# openTPM-v12.net
KiCad netlist of a schematic drawn in EAGLE
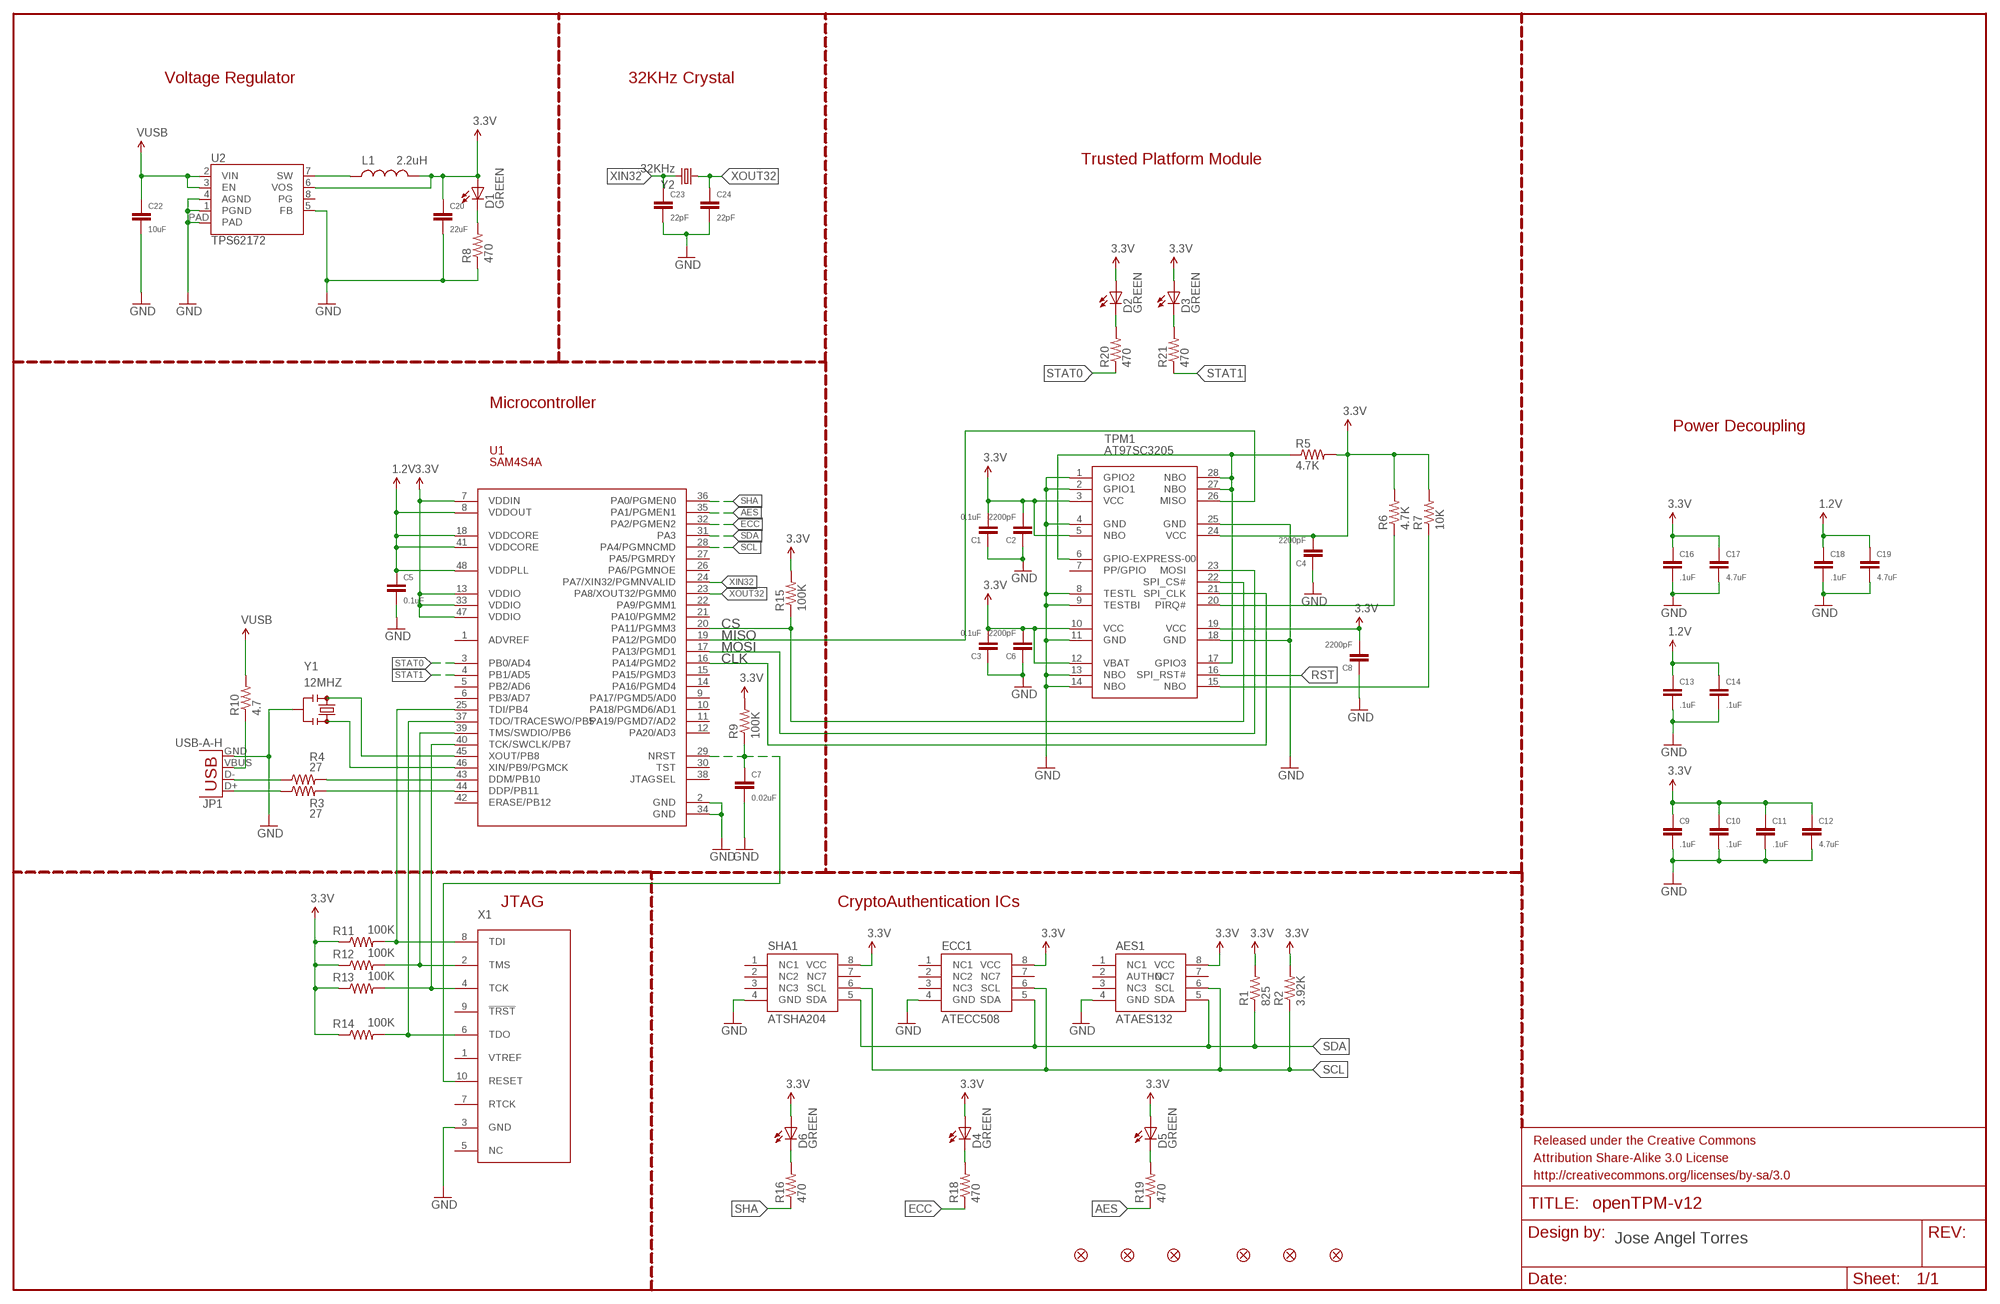
[diagram p0: schematic, sheet 1]

(export (version "E")
  (design (tool "Eeschema 10.0.6"))
  (components
    (comp (ref "AES1")
      (value "ATAES132")
      (footprint "eagle-import:CRYPTOTRONIX_SOIC8")
      (libsource (lib "eagle-import") (part "CRYPTOTRONIX_ATAES132"))
    )
    (comp (ref "C1")
      (value "0.1uF")
      (footprint "eagle-import:0201")
      (libsource (lib "eagle-import") (part "CAPACITOR.0201"))
    )
    (comp (ref "C2")
      (value "2200pF")
      (footprint "eagle-import:0201")
      (libsource (lib "eagle-import") (part "CAPACITOR.0201"))
    )
    (comp (ref "C3")
      (value "0.1uF")
      (footprint "eagle-import:0201")
      (libsource (lib "eagle-import") (part "CAPACITOR.0201"))
    )
    (comp (ref "C4")
      (value "2200pF")
      (footprint "eagle-import:0201")
      (libsource (lib "eagle-import") (part "CAPACITOR.0201"))
    )
    (comp (ref "C5")
      (value "0.1uF")
      (footprint "eagle-import:0201")
      (libsource (lib "eagle-import") (part "CAPACITOR.0201"))
    )
    (comp (ref "C6")
      (value "2200pF")
      (footprint "eagle-import:0201")
      (libsource (lib "eagle-import") (part "CAPACITOR.0201"))
    )
    (comp (ref "C7")
      (value "0.02uF")
      (footprint "eagle-import:0201")
      (libsource (lib "eagle-import") (part "CAPACITOR.0201"))
    )
    (comp (ref "C8")
      (value "2200pF")
      (footprint "eagle-import:0201")
      (libsource (lib "eagle-import") (part "CAPACITOR.0201"))
    )
    (comp (ref "C9")
      (value ".1uF")
      (footprint "eagle-import:0201")
      (libsource (lib "eagle-import") (part "CAPACITOR.0201"))
    )
    (comp (ref "C10")
      (value ".1uF")
      (footprint "eagle-import:0201")
      (libsource (lib "eagle-import") (part "CAPACITOR.0201"))
    )
    (comp (ref "C11")
      (value ".1uF")
      (footprint "eagle-import:0201")
      (libsource (lib "eagle-import") (part "CAPACITOR.0201"))
    )
    (comp (ref "C12")
      (value "4.7uF")
      (footprint "eagle-import:0402")
      (libsource (lib "eagle-import") (part "CAPACITOR.0402"))
    )
    (comp (ref "C13")
      (value ".1uF")
      (footprint "eagle-import:0201")
      (libsource (lib "eagle-import") (part "CAPACITOR.0201"))
    )
    (comp (ref "C14")
      (value ".1uF")
      (footprint "eagle-import:0201")
      (libsource (lib "eagle-import") (part "CAPACITOR.0201"))
    )
    (comp (ref "C16")
      (value ".1uF")
      (footprint "eagle-import:0201")
      (libsource (lib "eagle-import") (part "CAPACITOR.0201"))
    )
    (comp (ref "C17")
      (value "4.7uF")
      (footprint "eagle-import:0402")
      (libsource (lib "eagle-import") (part "CAPACITOR.0402"))
    )
    (comp (ref "C18")
      (value ".1uF")
      (footprint "eagle-import:0201")
      (libsource (lib "eagle-import") (part "CAPACITOR.0201"))
    )
    (comp (ref "C19")
      (value "4.7uF")
      (footprint "eagle-import:0402")
      (libsource (lib "eagle-import") (part "CAPACITOR.0402"))
    )
    (comp (ref "C20")
      (value "22uF")
      (footprint "eagle-import:0603")
      (libsource (lib "eagle-import") (part "CAPACITOR.0603"))
    )
    (comp (ref "C22")
      (value "10uF")
      (footprint "eagle-import:0402")
      (libsource (lib "eagle-import") (part "CAPACITOR.0402"))
    )
    (comp (ref "C23")
      (value "22pF")
      (footprint "eagle-import:0201")
      (libsource (lib "eagle-import") (part "CAPACITOR.0201"))
    )
    (comp (ref "C24")
      (value "22pF")
      (footprint "eagle-import:0201")
      (libsource (lib "eagle-import") (part "CAPACITOR.0201"))
    )
    (comp (ref "D1")
      (value "GREEN")
      (footprint "eagle-import:SPARKFUN-LED_LED-0603")
      (libsource (lib "eagle-import") (part "SPARKFUN-LED_LED-GREEN0603"))
    )
    (comp (ref "D2")
      (value "GREEN")
      (footprint "eagle-import:SPARKFUN-LED_LED-0603")
      (libsource (lib "eagle-import") (part "SPARKFUN-LED_LED-GREEN0603"))
    )
    (comp (ref "D3")
      (value "GREEN")
      (footprint "eagle-import:SPARKFUN-LED_LED-0603")
      (libsource (lib "eagle-import") (part "SPARKFUN-LED_LED-GREEN0603"))
    )
    (comp (ref "D4")
      (value "GREEN")
      (footprint "eagle-import:SPARKFUN-LED_LED-0603")
      (libsource (lib "eagle-import") (part "SPARKFUN-LED_LED-GREEN0603"))
    )
    (comp (ref "D5")
      (value "GREEN")
      (footprint "eagle-import:SPARKFUN-LED_LED-0603")
      (libsource (lib "eagle-import") (part "SPARKFUN-LED_LED-GREEN0603"))
    )
    (comp (ref "D6")
      (value "GREEN")
      (footprint "eagle-import:SPARKFUN-LED_LED-0603")
      (libsource (lib "eagle-import") (part "SPARKFUN-LED_LED-GREEN0603"))
    )
    (comp (ref "ECC1")
      (value "ATECC508")
      (footprint "eagle-import:CRYPTOTRONIX_SOIC8")
      (libsource (lib "eagle-import") (part "ATECC508"))
    )
    (comp (ref "FID1")
      (value "SPARKFUN-AESTHETICS_FIDUCIAL1X2")
      (footprint "eagle-import:SPARKFUN-AESTHETICS_FIDUCIAL-1X2")
      (libsource (lib "eagle-import") (part "SPARKFUN-AESTHETICS_FIDUCIAL1X2"))
    )
    (comp (ref "FID2")
      (value "SPARKFUN-AESTHETICS_FIDUCIAL1X2")
      (footprint "eagle-import:SPARKFUN-AESTHETICS_FIDUCIAL-1X2")
      (libsource (lib "eagle-import") (part "SPARKFUN-AESTHETICS_FIDUCIAL1X2"))
    )
    (comp (ref "FID3")
      (value "SPARKFUN-AESTHETICS_FIDUCIAL1X2")
      (footprint "eagle-import:SPARKFUN-AESTHETICS_FIDUCIAL-1X2")
      (libsource (lib "eagle-import") (part "SPARKFUN-AESTHETICS_FIDUCIAL1X2"))
    )
    (comp (ref "FID4")
      (value "SPARKFUN-AESTHETICS_FIDUCIAL1X2")
      (footprint "eagle-import:SPARKFUN-AESTHETICS_FIDUCIAL-1X2")
      (libsource (lib "eagle-import") (part "SPARKFUN-AESTHETICS_FIDUCIAL1X2"))
    )
    (comp (ref "FID5")
      (value "SPARKFUN-AESTHETICS_FIDUCIAL1X2")
      (footprint "eagle-import:SPARKFUN-AESTHETICS_FIDUCIAL-1X2")
      (libsource (lib "eagle-import") (part "SPARKFUN-AESTHETICS_FIDUCIAL1X2"))
    )
    (comp (ref "FID6")
      (value "SPARKFUN-AESTHETICS_FIDUCIAL1X2")
      (footprint "eagle-import:SPARKFUN-AESTHETICS_FIDUCIAL-1X2")
      (libsource (lib "eagle-import") (part "SPARKFUN-AESTHETICS_FIDUCIAL1X2"))
    )
    (comp (ref "JP1")
      (value "USB-A-H")
      (footprint "eagle-import:USB-A-H")
      (libsource (lib "eagle-import") (part "USB-A-H"))
    )
    (comp (ref "L1")
      (value "2.2uH")
      (footprint "eagle-import:C0402")
      (libsource (lib "eagle-import") (part "INDUCTOR0402"))
    )
    (comp (ref "R1")
      (value "825")
      (footprint "eagle-import:0201")
      (libsource (lib "eagle-import") (part "RESISTOR.0201"))
    )
    (comp (ref "R2")
      (value "3.92K")
      (footprint "eagle-import:0201")
      (libsource (lib "eagle-import") (part "RESISTOR.0201"))
    )
    (comp (ref "R3")
      (value "27")
      (footprint "eagle-import:0402")
      (libsource (lib "eagle-import") (part "RESISTOR.0402"))
    )
    (comp (ref "R4")
      (value "27")
      (footprint "eagle-import:0402")
      (libsource (lib "eagle-import") (part "RESISTOR.0402"))
    )
    (comp (ref "R5")
      (value "4.7K")
      (footprint "eagle-import:0201")
      (libsource (lib "eagle-import") (part "RESISTOR.0201"))
    )
    (comp (ref "R6")
      (value "4.7K")
      (footprint "eagle-import:0201")
      (libsource (lib "eagle-import") (part "RESISTOR.0201"))
    )
    (comp (ref "R7")
      (value "10K")
      (footprint "eagle-import:0201")
      (libsource (lib "eagle-import") (part "RESISTOR.0201"))
    )
    (comp (ref "R8")
      (value "470")
      (footprint "eagle-import:0402")
      (libsource (lib "eagle-import") (part "RESISTOR.0402"))
    )
    (comp (ref "R9")
      (value "100K")
      (footprint "eagle-import:0201")
      (libsource (lib "eagle-import") (part "RESISTOR.0201"))
    )
    (comp (ref "R10")
      (value "4.7")
      (footprint "eagle-import:0402")
      (libsource (lib "eagle-import") (part "RESISTOR.0402"))
    )
    (comp (ref "R11")
      (value "100K")
      (footprint "eagle-import:0201")
      (libsource (lib "eagle-import") (part "RESISTOR.0201"))
    )
    (comp (ref "R12")
      (value "100K")
      (footprint "eagle-import:0201")
      (libsource (lib "eagle-import") (part "RESISTOR.0201"))
    )
    (comp (ref "R13")
      (value "100K")
      (footprint "eagle-import:0201")
      (libsource (lib "eagle-import") (part "RESISTOR.0201"))
    )
    (comp (ref "R14")
      (value "100K")
      (footprint "eagle-import:0201")
      (libsource (lib "eagle-import") (part "RESISTOR.0201"))
    )
    (comp (ref "R15")
      (value "100K")
      (footprint "eagle-import:0201")
      (libsource (lib "eagle-import") (part "RESISTOR.0201"))
    )
    (comp (ref "R16")
      (value "470")
      (footprint "eagle-import:0201")
      (libsource (lib "eagle-import") (part "RESISTOR.0201"))
    )
    (comp (ref "R18")
      (value "470")
      (footprint "eagle-import:0201")
      (libsource (lib "eagle-import") (part "RESISTOR.0201"))
    )
    (comp (ref "R19")
      (value "470")
      (footprint "eagle-import:0201")
      (libsource (lib "eagle-import") (part "RESISTOR.0201"))
    )
    (comp (ref "R20")
      (value "470")
      (footprint "eagle-import:0201")
      (libsource (lib "eagle-import") (part "RESISTOR.0201"))
    )
    (comp (ref "R21")
      (value "470")
      (footprint "eagle-import:0201")
      (libsource (lib "eagle-import") (part "RESISTOR.0201"))
    )
    (comp (ref "SHA1")
      (value "ATSHA204")
      (footprint "eagle-import:CRYPTOTRONIX_SOIC8")
      (libsource (lib "eagle-import") (part "CRYPTOTRONIX_ATSHA204"))
    )
    (comp (ref "TPM1")
      (value "AT97SC3205")
      (footprint "eagle-import:TSSOP28")
      (libsource (lib "eagle-import") (part "AT97SC3205"))
    )
    (comp (ref "U1")
      (value "SAM4S4A")
      (footprint "eagle-import:LQFP-48")
      (libsource (lib "eagle-import") (part "SAM4S4A"))
    )
    (comp (ref "U2")
      (value "TPS62172")
      (footprint "eagle-import:WSON-8-PAD")
      (libsource (lib "eagle-import") (part "TPS62172"))
    )
    (comp (ref "X1")
      (value "TC2050-NL-MCP-NL")
      (footprint "eagle-import:TC2030-MCP-NL")
      (libsource (lib "eagle-import") (part "TC2050-NL-MCP-NL"))
    )
    (comp (ref "Y1")
      (value "12MHZ")
      (footprint "eagle-import:RESONATOR-SMD")
      (libsource (lib "eagle-import") (part "RESONATOR12MHZ"))
    )
    (comp (ref "Y2")
      (value "32KHz")
      (footprint "eagle-import:CRYSTAL-32KHZ-SMD_EPSON_MC146")
      (libsource (lib "eagle-import") (part "CRYSTALEPSONMC146"))
    )
  )
  (nets
    (net (code "1") (name "/CLK") (class "Default")
      (node (ref "TPM1") (pin "21") (pinfunction "SPI_CLK_21") (pintype "bidirectional"))
      (node (ref "U1") (pin "16") (pinfunction "PA14/PGMD2_16") (pintype "bidirectional"))
    )
    (net (code "2") (name "/CS") (class "Default")
      (node (ref "R15") (pin "1") (pinfunction "1_1") (pintype "passive"))
      (node (ref "TPM1") (pin "22") (pinfunction "SPI_CS#_22") (pintype "power_in"))
      (node (ref "U1") (pin "20") (pinfunction "PA11/PGMM3_20") (pintype "bidirectional"))
    )
    (net (code "3") (name "/MISO") (class "Default")
      (node (ref "TPM1") (pin "26") (pinfunction "MISO_26") (pintype "power_in"))
      (node (ref "U1") (pin "19") (pinfunction "PA12/PGMD0_19") (pintype "bidirectional"))
    )
    (net (code "4") (name "/MOSI") (class "Default")
      (node (ref "TPM1") (pin "23") (pinfunction "MOSI_23") (pintype "power_in"))
      (node (ref "U1") (pin "17") (pinfunction "PA13/PGMD1_17") (pintype "bidirectional"))
    )
    (net (code "5") (name "1.2V") (class "Default")
      (node (ref "C13") (pin "1") (pinfunction "1_1") (pintype "passive"))
      (node (ref "C14") (pin "1") (pinfunction "1_1") (pintype "passive"))
      (node (ref "C18") (pin "1") (pinfunction "1_1") (pintype "passive"))
      (node (ref "C19") (pin "1") (pinfunction "1_1") (pintype "passive"))
      (node (ref "C5") (pin "1") (pinfunction "1_1") (pintype "passive"))
      (node (ref "U1") (pin "18") (pinfunction "VDDCORE_18") (pintype "bidirectional"))
      (node (ref "U1") (pin "41") (pinfunction "VDDCORE_41") (pintype "bidirectional"))
      (node (ref "U1") (pin "48") (pinfunction "VDDPLL_48") (pintype "bidirectional"))
      (node (ref "U1") (pin "8") (pinfunction "VDDOUT_8") (pintype "bidirectional"))
    )
    (net (code "6") (name "3.3V") (class "Default")
      (node (ref "AES1") (pin "8") (pinfunction "VCC_8") (pintype "power_in"))
      (node (ref "C1") (pin "2") (pinfunction "2_2") (pintype "passive"))
      (node (ref "C10") (pin "1") (pinfunction "1_1") (pintype "passive"))
      (node (ref "C11") (pin "1") (pinfunction "1_1") (pintype "passive"))
      (node (ref "C12") (pin "1") (pinfunction "1_1") (pintype "passive"))
      (node (ref "C16") (pin "1") (pinfunction "1_1") (pintype "passive"))
      (node (ref "C17") (pin "1") (pinfunction "1_1") (pintype "passive"))
      (node (ref "C2") (pin "2") (pinfunction "2_2") (pintype "passive"))
      (node (ref "C20") (pin "1") (pinfunction "1_1") (pintype "passive"))
      (node (ref "C3") (pin "2") (pinfunction "2_2") (pintype "passive"))
      (node (ref "C4") (pin "2") (pinfunction "2_2") (pintype "passive"))
      (node (ref "C6") (pin "2") (pinfunction "2_2") (pintype "passive"))
      (node (ref "C8") (pin "2") (pinfunction "2_2") (pintype "passive"))
      (node (ref "C9") (pin "1") (pinfunction "1_1") (pintype "passive"))
      (node (ref "D1") (pin "A") (pinfunction "A_A") (pintype "passive"))
      (node (ref "D2") (pin "A") (pinfunction "A_A") (pintype "passive"))
      (node (ref "D3") (pin "A") (pinfunction "A_A") (pintype "passive"))
      (node (ref "D4") (pin "A") (pinfunction "A_A") (pintype "passive"))
      (node (ref "D5") (pin "A") (pinfunction "A_A") (pintype "passive"))
      (node (ref "D6") (pin "A") (pinfunction "A_A") (pintype "passive"))
      (node (ref "ECC1") (pin "8") (pinfunction "VCC_8") (pintype "power_in"))
      (node (ref "L1") (pin "2") (pinfunction "2_2") (pintype "passive"))
      (node (ref "R1") (pin "2") (pinfunction "2_2") (pintype "passive"))
      (node (ref "R11") (pin "1") (pinfunction "1_1") (pintype "passive"))
      (node (ref "R12") (pin "1") (pinfunction "1_1") (pintype "passive"))
      (node (ref "R13") (pin "1") (pinfunction "1_1") (pintype "passive"))
      (node (ref "R14") (pin "1") (pinfunction "1_1") (pintype "passive"))
      (node (ref "R15") (pin "2") (pinfunction "2_2") (pintype "passive"))
      (node (ref "R2") (pin "2") (pinfunction "2_2") (pintype "passive"))
      (node (ref "R5") (pin "2") (pinfunction "2_2") (pintype "passive"))
      (node (ref "R6") (pin "2") (pinfunction "2_2") (pintype "passive"))
      (node (ref "R7") (pin "2") (pinfunction "2_2") (pintype "passive"))
      (node (ref "R9") (pin "2") (pinfunction "2_2") (pintype "passive"))
      (node (ref "SHA1") (pin "8") (pinfunction "VCC_8") (pintype "power_in"))
      (node (ref "TPM1") (pin "10") (pinfunction "VCC_10") (pintype "power_in"))
      (node (ref "TPM1") (pin "12") (pinfunction "VBAT_12") (pintype "bidirectional"))
      (node (ref "TPM1") (pin "19") (pinfunction "VCC_19") (pintype "power_in"))
      (node (ref "TPM1") (pin "24") (pinfunction "VCC_24") (pintype "power_in"))
      (node (ref "TPM1") (pin "3") (pinfunction "VCC_3") (pintype "power_in"))
      (node (ref "TPM1") (pin "5") (pinfunction "NBO_5") (pintype "bidirectional"))
      (node (ref "U1") (pin "13") (pinfunction "VDDIO_13") (pintype "bidirectional"))
      (node (ref "U1") (pin "33") (pinfunction "VDDIO_33") (pintype "bidirectional"))
      (node (ref "U1") (pin "47") (pinfunction "VDDIO_47") (pintype "bidirectional"))
      (node (ref "U1") (pin "7") (pinfunction "VDDIN_7") (pintype "bidirectional"))
      (node (ref "U2") (pin "6") (pinfunction "VOS_6") (pintype "bidirectional"))
    )
    (net (code "7") (name "AES") (class "Default")
      (node (ref "R19") (pin "1") (pinfunction "1_1") (pintype "passive"))
      (node (ref "U1") (pin "35") (pinfunction "PA1/PGMEN1_35") (pintype "bidirectional"))
    )
    (net (code "8") (name "ECC") (class "Default")
      (node (ref "R18") (pin "1") (pinfunction "1_1") (pintype "passive"))
      (node (ref "U1") (pin "32") (pinfunction "PA2/PGMEN2_32") (pintype "bidirectional"))
    )
    (net (code "9") (name "GND") (class "Default")
      (node (ref "AES1") (pin "4") (pinfunction "GND_4") (pintype "power_in"))
      (node (ref "C1") (pin "1") (pinfunction "1_1") (pintype "passive"))
      (node (ref "C10") (pin "2") (pinfunction "2_2") (pintype "passive"))
      (node (ref "C11") (pin "2") (pinfunction "2_2") (pintype "passive"))
      (node (ref "C12") (pin "2") (pinfunction "2_2") (pintype "passive"))
      (node (ref "C13") (pin "2") (pinfunction "2_2") (pintype "passive"))
      (node (ref "C14") (pin "2") (pinfunction "2_2") (pintype "passive"))
      (node (ref "C16") (pin "2") (pinfunction "2_2") (pintype "passive"))
      (node (ref "C17") (pin "2") (pinfunction "2_2") (pintype "passive"))
      (node (ref "C18") (pin "2") (pinfunction "2_2") (pintype "passive"))
      (node (ref "C19") (pin "2") (pinfunction "2_2") (pintype "passive"))
      (node (ref "C2") (pin "1") (pinfunction "1_1") (pintype "passive"))
      (node (ref "C20") (pin "2") (pinfunction "2_2") (pintype "passive"))
      (node (ref "C22") (pin "2") (pinfunction "2_2") (pintype "passive"))
      (node (ref "C23") (pin "2") (pinfunction "2_2") (pintype "passive"))
      (node (ref "C24") (pin "2") (pinfunction "2_2") (pintype "passive"))
      (node (ref "C3") (pin "1") (pinfunction "1_1") (pintype "passive"))
      (node (ref "C4") (pin "1") (pinfunction "1_1") (pintype "passive"))
      (node (ref "C5") (pin "2") (pinfunction "2_2") (pintype "passive"))
      (node (ref "C6") (pin "1") (pinfunction "1_1") (pintype "passive"))
      (node (ref "C7") (pin "2") (pinfunction "2_2") (pintype "passive"))
      (node (ref "C8") (pin "1") (pinfunction "1_1") (pintype "passive"))
      (node (ref "C9") (pin "2") (pinfunction "2_2") (pintype "passive"))
      (node (ref "ECC1") (pin "4") (pinfunction "GND_4") (pintype "power_in"))
      (node (ref "JP1") (pin "GND") (pinfunction "GND_GND") (pintype "bidirectional"))
      (node (ref "R8") (pin "1") (pinfunction "1_1") (pintype "passive"))
      (node (ref "SHA1") (pin "4") (pinfunction "GND_4") (pintype "power_in"))
      (node (ref "TPM1") (pin "1") (pinfunction "GPIO2_1") (pintype "bidirectional"))
      (node (ref "TPM1") (pin "11") (pinfunction "GND_11") (pintype "power_in"))
      (node (ref "TPM1") (pin "13") (pinfunction "NBO_13") (pintype "bidirectional"))
      (node (ref "TPM1") (pin "14") (pinfunction "NBO_14") (pintype "bidirectional"))
      (node (ref "TPM1") (pin "18") (pinfunction "GND_18") (pintype "power_in"))
      (node (ref "TPM1") (pin "2") (pinfunction "GPIO1_2") (pintype "bidirectional"))
      (node (ref "TPM1") (pin "25") (pinfunction "GND_25") (pintype "power_in"))
      (node (ref "TPM1") (pin "4") (pinfunction "GND_4") (pintype "power_in"))
      (node (ref "TPM1") (pin "8") (pinfunction "TESTL_8") (pintype "bidirectional"))
      (node (ref "TPM1") (pin "9") (pinfunction "TESTBI_9") (pintype "bidirectional"))
      (node (ref "U1") (pin "2") (pinfunction "GND_2") (pintype "bidirectional"))
      (node (ref "U1") (pin "34") (pinfunction "GND_34") (pintype "bidirectional"))
      (node (ref "U2") (pin "1") (pinfunction "PGND_1") (pintype "bidirectional"))
      (node (ref "U2") (pin "4") (pinfunction "AGND_4") (pintype "bidirectional"))
      (node (ref "U2") (pin "5") (pinfunction "FB_5") (pintype "bidirectional"))
      (node (ref "U2") (pin "PAD") (pinfunction "PAD_PAD") (pintype "bidirectional"))
      (node (ref "X1") (pin "3") (pinfunction "GND_3") (pintype "bidirectional"))
      (node (ref "Y1") (pin "2") (pinfunction "2_2") (pintype "passive"))
    )
    (net (code "10") (name "Net-(D1-PadC)") (class "Default")
      (node (ref "D1") (pin "C") (pinfunction "C_C") (pintype "passive"))
      (node (ref "R8") (pin "2") (pinfunction "2_2") (pintype "passive"))
    )
    (net (code "11") (name "Net-(D2-PadC)") (class "Default")
      (node (ref "D2") (pin "C") (pinfunction "C_C") (pintype "passive"))
      (node (ref "R20") (pin "2") (pinfunction "2_2") (pintype "passive"))
    )
    (net (code "12") (name "Net-(D3-PadC)") (class "Default")
      (node (ref "D3") (pin "C") (pinfunction "C_C") (pintype "passive"))
      (node (ref "R21") (pin "2") (pinfunction "2_2") (pintype "passive"))
    )
    (net (code "13") (name "Net-(D4-PadC)") (class "Default")
      (node (ref "D4") (pin "C") (pinfunction "C_C") (pintype "passive"))
      (node (ref "R18") (pin "2") (pinfunction "2_2") (pintype "passive"))
    )
    (net (code "14") (name "Net-(D5-PadC)") (class "Default")
      (node (ref "D5") (pin "C") (pinfunction "C_C") (pintype "passive"))
      (node (ref "R19") (pin "2") (pinfunction "2_2") (pintype "passive"))
    )
    (net (code "15") (name "Net-(D6-PadC)") (class "Default")
      (node (ref "D6") (pin "C") (pinfunction "C_C") (pintype "passive"))
      (node (ref "R16") (pin "2") (pinfunction "2_2") (pintype "passive"))
    )
    (net (code "16") (name "Net-(JP1-PadD+)") (class "Default")
      (node (ref "JP1") (pin "D+") (pinfunction "D+_D+") (pintype "bidirectional"))
      (node (ref "R3") (pin "1") (pinfunction "1_1") (pintype "passive"))
    )
    (net (code "17") (name "Net-(JP1-PadD-)") (class "Default")
      (node (ref "JP1") (pin "D-") (pinfunction "D-_D-") (pintype "bidirectional"))
      (node (ref "R4") (pin "1") (pinfunction "1_1") (pintype "passive"))
    )
    (net (code "18") (name "Net-(JP1-PadVBUS)") (class "Default")
      (node (ref "JP1") (pin "VBUS") (pinfunction "VBUS_VBUS") (pintype "bidirectional"))
      (node (ref "R10") (pin "1") (pinfunction "1_1") (pintype "passive"))
    )
    (net (code "19") (name "Net-(R7-Pad1)") (class "Default")
      (node (ref "R7") (pin "1") (pinfunction "1_1") (pintype "passive"))
      (node (ref "TPM1") (pin "15") (pinfunction "NBO_15") (pintype "bidirectional"))
    )
    (net (code "20") (name "Net-(TPM1-GPIO-EXPRESS-00)") (class "Default")
      (node (ref "R5") (pin "1") (pinfunction "1_1") (pintype "passive"))
      (node (ref "TPM1") (pin "17") (pinfunction "GPIO3_17") (pintype "power_in"))
      (node (ref "TPM1") (pin "27") (pinfunction "NBO_27") (pintype "bidirectional"))
      (node (ref "TPM1") (pin "28") (pinfunction "NBO_28") (pintype "bidirectional"))
      (node (ref "TPM1") (pin "6") (pinfunction "GPIO-EXPRESS-00_6") (pintype "power_in"))
    )
    (net (code "21") (name "Net-(TPM1-PIRQ#)") (class "Default")
      (node (ref "R6") (pin "1") (pinfunction "1_1") (pintype "passive"))
      (node (ref "TPM1") (pin "20") (pinfunction "PIRQ#_20") (pintype "power_in"))
    )
    (net (code "22") (name "Net-(U1-DDM{slash}PB10)") (class "Default")
      (node (ref "R4") (pin "2") (pinfunction "2_2") (pintype "passive"))
      (node (ref "U1") (pin "43") (pinfunction "DDM/PB10_43") (pintype "bidirectional"))
    )
    (net (code "23") (name "Net-(U1-DDP{slash}PB11)") (class "Default")
      (node (ref "R3") (pin "2") (pinfunction "2_2") (pintype "passive"))
      (node (ref "U1") (pin "44") (pinfunction "DDP/PB11_44") (pintype "bidirectional"))
    )
    (net (code "24") (name "Net-(U1-TCK{slash}SWCLK{slash}PB7)") (class "Default")
      (node (ref "R13") (pin "2") (pinfunction "2_2") (pintype "passive"))
      (node (ref "U1") (pin "40") (pinfunction "TCK/SWCLK/PB7_40") (pintype "bidirectional"))
      (node (ref "X1") (pin "4") (pinfunction "TCK_4") (pintype "bidirectional"))
    )
    (net (code "25") (name "Net-(U1-TDI{slash}PB4)") (class "Default")
      (node (ref "R11") (pin "2") (pinfunction "2_2") (pintype "passive"))
      (node (ref "U1") (pin "25") (pinfunction "TDI/PB4_25") (pintype "bidirectional"))
      (node (ref "X1") (pin "8") (pinfunction "TDI_8") (pintype "bidirectional"))
    )
    (net (code "26") (name "Net-(U1-TDO{slash}TRACESWO{slash}PB5)") (class "Default")
      (node (ref "R14") (pin "2") (pinfunction "2_2") (pintype "passive"))
      (node (ref "U1") (pin "37") (pinfunction "TDO/TRACESWO/PB5_37") (pintype "bidirectional"))
      (node (ref "X1") (pin "6") (pinfunction "TDO_6") (pintype "bidirectional"))
    )
    (net (code "27") (name "Net-(U1-TMS{slash}SWDIO{slash}PB6)") (class "Default")
      (node (ref "R12") (pin "2") (pinfunction "2_2") (pintype "passive"))
      (node (ref "U1") (pin "39") (pinfunction "TMS/SWDIO/PB6_39") (pintype "bidirectional"))
      (node (ref "X1") (pin "2") (pinfunction "TMS_2") (pintype "bidirectional"))
    )
    (net (code "28") (name "Net-(U1-XIN{slash}PB9{slash}PGMCK)") (class "Default")
      (node (ref "U1") (pin "46") (pinfunction "XIN/PB9/PGMCK_46") (pintype "bidirectional"))
      (node (ref "Y1") (pin "3") (pinfunction "3_3") (pintype "passive"))
    )
    (net (code "29") (name "Net-(U1-XOUT{slash}PB8)") (class "Default")
      (node (ref "U1") (pin "45") (pinfunction "XOUT/PB8_45") (pintype "bidirectional"))
      (node (ref "Y1") (pin "1") (pinfunction "1_1") (pintype "passive"))
    )
    (net (code "30") (name "Net-(U2-SW)") (class "Default")
      (node (ref "L1") (pin "1") (pinfunction "1_1") (pintype "passive"))
      (node (ref "U2") (pin "7") (pinfunction "SW_7") (pintype "bidirectional"))
    )
    (net (code "31") (name "RST") (class "Default")
      (node (ref "C7") (pin "1") (pinfunction "1_1") (pintype "passive"))
      (node (ref "R9") (pin "1") (pinfunction "1_1") (pintype "passive"))
      (node (ref "TPM1") (pin "16") (pinfunction "SPI_RST#_16") (pintype "bidirectional"))
      (node (ref "U1") (pin "29") (pinfunction "NRST_29") (pintype "bidirectional"))
      (node (ref "X1") (pin "10") (pinfunction "RESET_10") (pintype "bidirectional"))
    )
    (net (code "32") (name "SCL") (class "Default")
      (node (ref "AES1") (pin "6") (pinfunction "SCL_6") (pintype "bidirectional"))
      (node (ref "ECC1") (pin "6") (pinfunction "SCL_6") (pintype "bidirectional"))
      (node (ref "R2") (pin "1") (pinfunction "1_1") (pintype "passive"))
      (node (ref "SHA1") (pin "6") (pinfunction "SCL_6") (pintype "bidirectional"))
      (node (ref "U1") (pin "28") (pinfunction "PA4/PGMNCMD_28") (pintype "bidirectional"))
    )
    (net (code "33") (name "SDA") (class "Default")
      (node (ref "AES1") (pin "5") (pinfunction "SDA_5") (pintype "bidirectional"))
      (node (ref "ECC1") (pin "5") (pinfunction "SDA_5") (pintype "bidirectional"))
      (node (ref "R1") (pin "1") (pinfunction "1_1") (pintype "passive"))
      (node (ref "SHA1") (pin "5") (pinfunction "SDA_5") (pintype "bidirectional"))
      (node (ref "U1") (pin "31") (pinfunction "PA3_31") (pintype "bidirectional"))
    )
    (net (code "34") (name "SHA") (class "Default")
      (node (ref "R16") (pin "1") (pinfunction "1_1") (pintype "passive"))
      (node (ref "U1") (pin "36") (pinfunction "PA0/PGMEN0_36") (pintype "bidirectional"))
    )
    (net (code "35") (name "STAT0") (class "Default")
      (node (ref "R20") (pin "1") (pinfunction "1_1") (pintype "passive"))
      (node (ref "U1") (pin "3") (pinfunction "PB0/AD4_3") (pintype "bidirectional"))
    )
    (net (code "36") (name "STAT1") (class "Default")
      (node (ref "R21") (pin "1") (pinfunction "1_1") (pintype "passive"))
      (node (ref "U1") (pin "4") (pinfunction "PB1/AD5_4") (pintype "bidirectional"))
    )
    (net (code "37") (name "VUSB") (class "Default")
      (node (ref "C22") (pin "1") (pinfunction "1_1") (pintype "passive"))
      (node (ref "R10") (pin "2") (pinfunction "2_2") (pintype "passive"))
      (node (ref "U2") (pin "2") (pinfunction "VIN_2") (pintype "bidirectional"))
      (node (ref "U2") (pin "3") (pinfunction "EN_3") (pintype "bidirectional"))
    )
    (net (code "38") (name "XIN32") (class "Default")
      (node (ref "C23") (pin "1") (pinfunction "1_1") (pintype "passive"))
      (node (ref "U1") (pin "24") (pinfunction "PA7/XIN32/PGMNVALID_24") (pintype "bidirectional"))
      (node (ref "Y2") (pin "P$1") (pinfunction "2_P$1") (pintype "passive"))
    )
    (net (code "39") (name "XOUT32") (class "Default")
      (node (ref "C24") (pin "1") (pinfunction "1_1") (pintype "passive"))
      (node (ref "U1") (pin "23") (pinfunction "PA8/XOUT32/PGMM0_23") (pintype "bidirectional"))
      (node (ref "Y2") (pin "P$2") (pinfunction "1_P$2") (pintype "passive"))
    )
    (net (code "40") (name "unconnected-(AES1-AUTHO-Pad2)") (class "Default")
      (node (ref "AES1") (pin "2") (pinfunction "AUTHO_2") (pintype "bidirectional"))
    )
    (net (code "41") (name "unconnected-(AES1-NC1-Pad1)") (class "Default")
      (node (ref "AES1") (pin "1") (pinfunction "NC1_1") (pintype "no_connect"))
    )
    (net (code "42") (name "unconnected-(AES1-NC3-Pad3)") (class "Default")
      (node (ref "AES1") (pin "3") (pinfunction "NC3_3") (pintype "no_connect"))
    )
    (net (code "43") (name "unconnected-(AES1-NC7-Pad7)") (class "Default")
      (node (ref "AES1") (pin "7") (pinfunction "NC7_7") (pintype "no_connect"))
    )
    (net (code "44") (name "unconnected-(ECC1-NC1-Pad1)") (class "Default")
      (node (ref "ECC1") (pin "1") (pinfunction "NC1_1") (pintype "bidirectional"))
    )
    (net (code "45") (name "unconnected-(ECC1-NC2-Pad2)") (class "Default")
      (node (ref "ECC1") (pin "2") (pinfunction "NC2_2") (pintype "no_connect"))
    )
    (net (code "46") (name "unconnected-(ECC1-NC3-Pad3)") (class "Default")
      (node (ref "ECC1") (pin "3") (pinfunction "NC3_3") (pintype "no_connect"))
    )
    (net (code "47") (name "unconnected-(ECC1-NC7-Pad7)") (class "Default")
      (node (ref "ECC1") (pin "7") (pinfunction "NC7_7") (pintype "no_connect"))
    )
    (net (code "48") (name "unconnected-(SHA1-NC1-Pad1)") (class "Default")
      (node (ref "SHA1") (pin "1") (pinfunction "NC1_1") (pintype "no_connect"))
    )
    (net (code "49") (name "unconnected-(SHA1-NC2-Pad2)") (class "Default")
      (node (ref "SHA1") (pin "2") (pinfunction "NC2_2") (pintype "no_connect"))
    )
    (net (code "50") (name "unconnected-(SHA1-NC3-Pad3)") (class "Default")
      (node (ref "SHA1") (pin "3") (pinfunction "NC3_3") (pintype "no_connect"))
    )
    (net (code "51") (name "unconnected-(SHA1-NC7-Pad7)") (class "Default")
      (node (ref "SHA1") (pin "7") (pinfunction "NC7_7") (pintype "no_connect"))
    )
    (net (code "52") (name "unconnected-(TPM1-PP{slash}GPIO-Pad7)") (class "Default")
      (node (ref "TPM1") (pin "7") (pinfunction "PP/GPIO_7") (pintype "bidirectional"))
    )
    (net (code "53") (name "unconnected-(U1-ADVREF-Pad1)") (class "Default")
      (node (ref "U1") (pin "1") (pinfunction "ADVREF_1") (pintype "bidirectional"))
    )
    (net (code "54") (name "unconnected-(U1-ERASE{slash}PB12-Pad42)") (class "Default")
      (node (ref "U1") (pin "42") (pinfunction "ERASE/PB12_42") (pintype "bidirectional"))
    )
    (net (code "55") (name "unconnected-(U1-JTAGSEL-Pad38)") (class "Default")
      (node (ref "U1") (pin "38") (pinfunction "JTAGSEL_38") (pintype "bidirectional"))
    )
    (net (code "56") (name "unconnected-(U1-PA5{slash}PGMRDY-Pad27)") (class "Default")
      (node (ref "U1") (pin "27") (pinfunction "PA5/PGMRDY_27") (pintype "bidirectional"))
    )
    (net (code "57") (name "unconnected-(U1-PA6{slash}PGMNOE-Pad26)") (class "Default")
      (node (ref "U1") (pin "26") (pinfunction "PA6/PGMNOE_26") (pintype "bidirectional"))
    )
    (net (code "58") (name "unconnected-(U1-PA9{slash}PGMM1-Pad22)") (class "Default")
      (node (ref "U1") (pin "22") (pinfunction "PA9/PGMM1_22") (pintype "bidirectional"))
    )
    (net (code "59") (name "unconnected-(U1-PA10{slash}PGMM2-Pad21)") (class "Default")
      (node (ref "U1") (pin "21") (pinfunction "PA10/PGMM2_21") (pintype "bidirectional"))
    )
    (net (code "60") (name "unconnected-(U1-PA15{slash}PGMD3-Pad15)") (class "Default")
      (node (ref "U1") (pin "15") (pinfunction "PA15/PGMD3_15") (pintype "bidirectional"))
    )
    (net (code "61") (name "unconnected-(U1-PA16{slash}PGMD4-Pad14)") (class "Default")
      (node (ref "U1") (pin "14") (pinfunction "PA16/PGMD4_14") (pintype "bidirectional"))
    )
    (net (code "62") (name "unconnected-(U1-PA17{slash}PGMD5{slash}AD0-Pad9)") (class "Default")
      (node (ref "U1") (pin "9") (pinfunction "PA17/PGMD5/AD0_9") (pintype "bidirectional"))
    )
    (net (code "63") (name "unconnected-(U1-PA18{slash}PGMD6{slash}AD1-Pad10)") (class "Default")
      (node (ref "U1") (pin "10") (pinfunction "PA18/PGMD6/AD1_10") (pintype "bidirectional"))
    )
    (net (code "64") (name "unconnected-(U1-PA19{slash}PGMD7{slash}AD2-Pad11)") (class "Default")
      (node (ref "U1") (pin "11") (pinfunction "PA19/PGMD7/AD2_11") (pintype "bidirectional"))
    )
    (net (code "65") (name "unconnected-(U1-PA20{slash}AD3-Pad12)") (class "Default")
      (node (ref "U1") (pin "12") (pinfunction "PA20/AD3_12") (pintype "bidirectional"))
    )
    (net (code "66") (name "unconnected-(U1-PB2{slash}AD6-Pad5)") (class "Default")
      (node (ref "U1") (pin "5") (pinfunction "PB2/AD6_5") (pintype "bidirectional"))
    )
    (net (code "67") (name "unconnected-(U1-PB3{slash}AD7-Pad6)") (class "Default")
      (node (ref "U1") (pin "6") (pinfunction "PB3/AD7_6") (pintype "bidirectional"))
    )
    (net (code "68") (name "unconnected-(U1-TST-Pad30)") (class "Default")
      (node (ref "U1") (pin "30") (pinfunction "TST_30") (pintype "bidirectional"))
    )
    (net (code "69") (name "unconnected-(U2-PG-Pad8)") (class "Default")
      (node (ref "U2") (pin "8") (pinfunction "PG_8") (pintype "bidirectional"))
    )
    (net (code "70") (name "unconnected-(X1-NC-Pad5)") (class "Default")
      (node (ref "X1") (pin "5") (pinfunction "NC_5") (pintype "bidirectional"))
    )
    (net (code "71") (name "unconnected-(X1-RTCK-Pad7)") (class "Default")
      (node (ref "X1") (pin "7") (pinfunction "RTCK_7") (pintype "bidirectional"))
    )
    (net (code "72") (name "unconnected-(X1-VTREF-Pad1)") (class "Default")
      (node (ref "X1") (pin "1") (pinfunction "VTREF_1") (pintype "bidirectional"))
    )
    (net (code "73") (name "unconnected-(X1-~{TRST}-Pad9)") (class "Default")
      (node (ref "X1") (pin "9") (pinfunction "~{TRST}_9") (pintype "bidirectional"))
    )
  )
)
